# ATmega128RFA1-dev.net
KiCad netlist of a schematic drawn in EAGLE
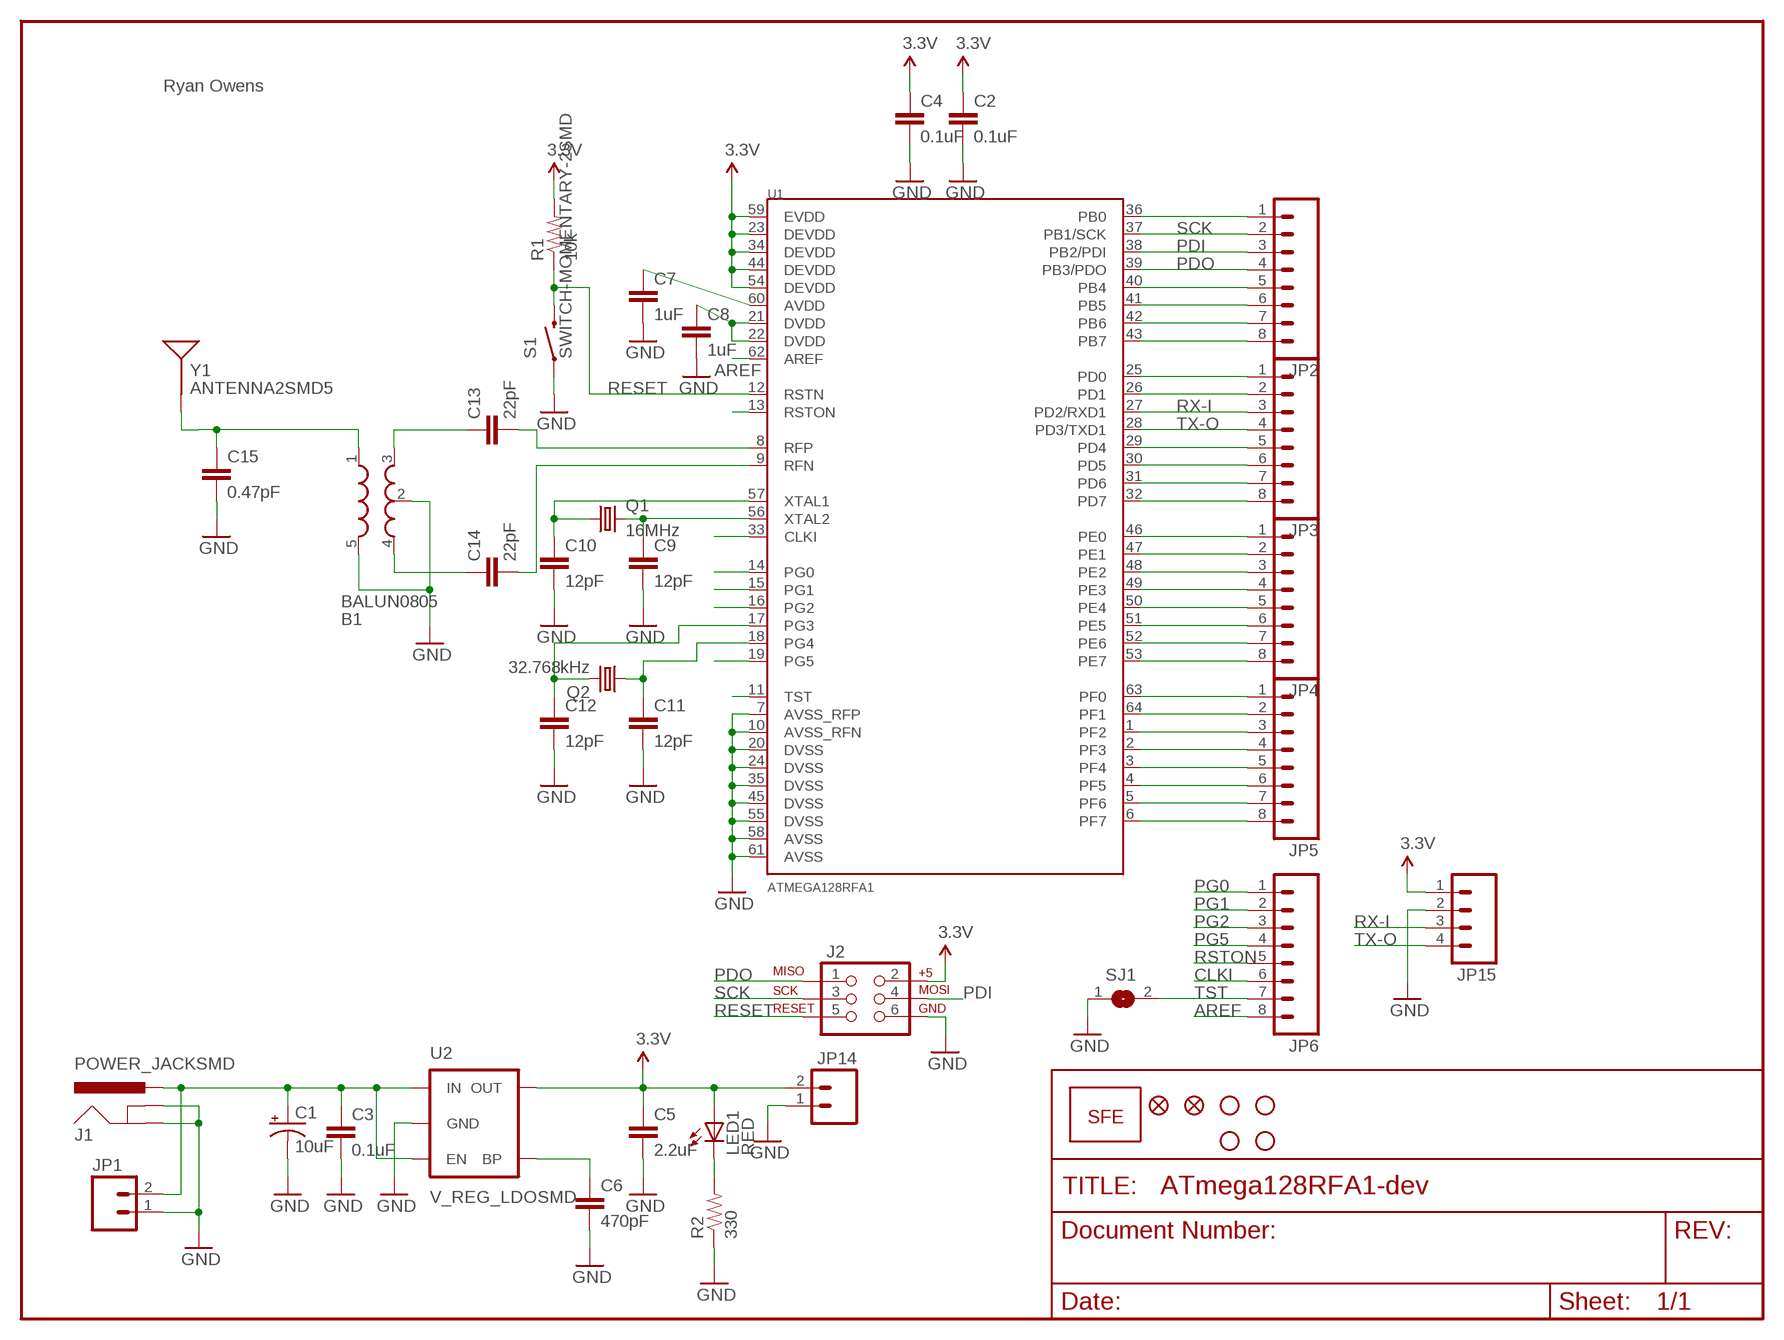
[diagram p0: schematic, sheet 1]

(export (version "E")
  (design (tool "Eeschema 10.0.6"))
  (components
    (comp (ref "B1")
      (value "BALUN0805")
      (footprint "eagle-import:BALUN")
      (libsource (lib "eagle-import") (part "BALUN0805"))
    )
    (comp (ref "C1")
      (value "10uF")
      (footprint "eagle-import:EIA3216")
      (libsource (lib "eagle-import") (part "CAP_POL1206"))
    )
    (comp (ref "C2")
      (value "0.1uF")
      (footprint "eagle-import:0603-CAP")
      (libsource (lib "eagle-import") (part "CAP0603-CAP"))
    )
    (comp (ref "C3")
      (value "0.1uF")
      (footprint "eagle-import:0603-CAP")
      (libsource (lib "eagle-import") (part "CAP0603-CAP"))
    )
    (comp (ref "C4")
      (value "0.1uF")
      (footprint "eagle-import:0603-CAP")
      (libsource (lib "eagle-import") (part "CAP0603-CAP"))
    )
    (comp (ref "C5")
      (value "2.2uF")
      (footprint "eagle-import:0603-CAP")
      (libsource (lib "eagle-import") (part "CAP0603-CAP"))
    )
    (comp (ref "C6")
      (value "470pF")
      (footprint "eagle-import:0603-CAP")
      (libsource (lib "eagle-import") (part "CAP0603-CAP"))
    )
    (comp (ref "C7")
      (value "1uF")
      (footprint "eagle-import:0805")
      (libsource (lib "eagle-import") (part "CAP0805"))
    )
    (comp (ref "C8")
      (value "1uF")
      (footprint "eagle-import:0805")
      (libsource (lib "eagle-import") (part "CAP0805"))
    )
    (comp (ref "C9")
      (value "12pF")
      (footprint "eagle-import:0603-CAP")
      (libsource (lib "eagle-import") (part "CAP0603-CAP"))
    )
    (comp (ref "C10")
      (value "12pF")
      (footprint "eagle-import:0603-CAP")
      (libsource (lib "eagle-import") (part "CAP0603-CAP"))
    )
    (comp (ref "C11")
      (value "12pF")
      (footprint "eagle-import:0603-CAP")
      (libsource (lib "eagle-import") (part "CAP0603-CAP"))
    )
    (comp (ref "C12")
      (value "12pF")
      (footprint "eagle-import:0603-CAP")
      (libsource (lib "eagle-import") (part "CAP0603-CAP"))
    )
    (comp (ref "C13")
      (value "22pF")
      (footprint "eagle-import:0603-CAP")
      (libsource (lib "eagle-import") (part "CAP0603-CAP"))
    )
    (comp (ref "C14")
      (value "22pF")
      (footprint "eagle-import:0603-CAP")
      (libsource (lib "eagle-import") (part "CAP0603-CAP"))
    )
    (comp (ref "C15")
      (value "0.47pF")
      (footprint "eagle-import:0603-CAP")
      (libsource (lib "eagle-import") (part "CAP0603-CAP"))
    )
    (comp (ref "J1")
      (value "POWER_JACKSMD")
      (footprint "eagle-import:POWER_JACK_SMD")
      (libsource (lib "eagle-import") (part "POWER_JACKSMD"))
    )
    (comp (ref "J2")
      (value "AVR_SPI_PRG_6PTH")
      (footprint "eagle-import:2X3")
      (libsource (lib "eagle-import") (part "AVR_SPI_PRG_6PTH"))
    )
    (comp (ref "JP1")
      (value "M02PTH")
      (footprint "eagle-import:1X02")
      (libsource (lib "eagle-import") (part "M02PTH"))
    )
    (comp (ref "JP2")
      (value "M08")
      (footprint "eagle-import:1X08")
      (libsource (lib "eagle-import") (part "M08"))
    )
    (comp (ref "JP3")
      (value "M08")
      (footprint "eagle-import:1X08")
      (libsource (lib "eagle-import") (part "M08"))
    )
    (comp (ref "JP4")
      (value "M08")
      (footprint "eagle-import:1X08")
      (libsource (lib "eagle-import") (part "M08"))
    )
    (comp (ref "JP5")
      (value "M08")
      (footprint "eagle-import:1X08")
      (libsource (lib "eagle-import") (part "M08"))
    )
    (comp (ref "JP6")
      (value "M08")
      (footprint "eagle-import:1X08")
      (libsource (lib "eagle-import") (part "M08"))
    )
    (comp (ref "JP7")
      (value "LOGO-SFENEW")
      (footprint "eagle-import:SFE-NEW-WEBLOGO")
      (libsource (lib "eagle-import") (part "LOGO-SFENEW"))
    )
    (comp (ref "JP8")
      (value "FIDUCIAL1X2")
      (footprint "eagle-import:FIDUCIAL-1X2")
      (libsource (lib "eagle-import") (part "FIDUCIAL1X2"))
    )
    (comp (ref "JP9")
      (value "FIDUCIAL1X2")
      (footprint "eagle-import:FIDUCIAL-1X2")
      (libsource (lib "eagle-import") (part "FIDUCIAL1X2"))
    )
    (comp (ref "JP10")
      (value "STAND-OFF")
      (footprint "eagle-import:STAND-OFF")
      (libsource (lib "eagle-import") (part "STAND-OFF"))
    )
    (comp (ref "JP11")
      (value "STAND-OFF")
      (footprint "eagle-import:STAND-OFF")
      (libsource (lib "eagle-import") (part "STAND-OFF"))
    )
    (comp (ref "JP12")
      (value "STAND-OFF")
      (footprint "eagle-import:STAND-OFF")
      (libsource (lib "eagle-import") (part "STAND-OFF"))
    )
    (comp (ref "JP13")
      (value "STAND-OFF")
      (footprint "eagle-import:STAND-OFF")
      (libsource (lib "eagle-import") (part "STAND-OFF"))
    )
    (comp (ref "JP14")
      (value "M02PTH")
      (footprint "eagle-import:1X02")
      (libsource (lib "eagle-import") (part "M02PTH"))
    )
    (comp (ref "JP15")
      (value "M04PTH")
      (footprint "eagle-import:1X04")
      (libsource (lib "eagle-import") (part "M04PTH"))
    )
    (comp (ref "LED1")
      (value "RED")
      (footprint "eagle-import:LED-0603")
      (libsource (lib "eagle-import") (part "LED0603"))
    )
    (comp (ref "Q1")
      (value "16MHz")
      (footprint "eagle-import:CRYSTAL-SMD-5X3")
      (libsource (lib "eagle-import") (part "CRYSTAL5X3"))
    )
    (comp (ref "Q2")
      (value "32.768kHz")
      (footprint "eagle-import:CRYSTAL-32KHZ-SMD")
      (libsource (lib "eagle-import") (part "CRYSTAL32-SMD"))
    )
    (comp (ref "R1")
      (value "10k")
      (footprint "eagle-import:0603-RES")
      (libsource (lib "eagle-import") (part "RESISTOR0603-RES"))
    )
    (comp (ref "R2")
      (value "330")
      (footprint "eagle-import:0603-RES")
      (libsource (lib "eagle-import") (part "RESISTOR0603-RES"))
    )
    (comp (ref "S1")
      (value "SWITCH-MOMENTARY-2SMD")
      (footprint "eagle-import:TACTILE_SWITCH_SMD")
      (libsource (lib "eagle-import") (part "SWITCH-MOMENTARY-2SMD"))
    )
    (comp (ref "SJ1") (value "SJ") (footprint "eagle-import:SJ") (libsource (lib "eagle-import") (part "SJ")))
    (comp (ref "U1")
      (value "ATMEGA128RFA1")
      (footprint "eagle-import:QFN-64")
      (libsource (lib "eagle-import") (part "ATMEGA128RFA1"))
    )
    (comp (ref "U2")
      (value "V_REG_LDOSMD")
      (footprint "eagle-import:SOT23-5")
      (libsource (lib "eagle-import") (part "V_REG_LDOSMD"))
    )
    (comp (ref "Y1")
      (value "ANTENNA2SMD5")
      (footprint "eagle-import:ANTENNA-CHIP5")
      (libsource (lib "eagle-import") (part "ANTENNA2SMD5"))
    )
  )
  (nets
    (net (code "1") (name "/AREF") (class "Default")
      (node (ref "JP6") (pin "8") (pinfunction "8_8") (pintype "passive"))
      (node (ref "U1") (pin "62") (pinfunction "AREF_62") (pintype "bidirectional"))
    )
    (net (code "2") (name "/CLKI") (class "Default")
      (node (ref "JP6") (pin "6") (pinfunction "6_6") (pintype "passive"))
      (node (ref "U1") (pin "33") (pinfunction "CLKI_33") (pintype "bidirectional"))
    )
    (net (code "3") (name "/PDI") (class "Default")
      (node (ref "J2") (pin "4") (pinfunction "4_4") (pintype "passive"))
      (node (ref "JP2") (pin "3") (pinfunction "3_3") (pintype "passive"))
      (node (ref "U1") (pin "38") (pinfunction "PB2/PDI_38") (pintype "bidirectional"))
    )
    (net (code "4") (name "/PDO") (class "Default")
      (node (ref "J2") (pin "1") (pinfunction "1_1") (pintype "passive"))
      (node (ref "JP2") (pin "4") (pinfunction "4_4") (pintype "passive"))
      (node (ref "U1") (pin "39") (pinfunction "PB3/PDO_39") (pintype "bidirectional"))
    )
    (net (code "5") (name "/PG0") (class "Default")
      (node (ref "JP6") (pin "1") (pinfunction "1_1") (pintype "passive"))
      (node (ref "U1") (pin "14") (pinfunction "PG0_14") (pintype "bidirectional"))
    )
    (net (code "6") (name "/PG1") (class "Default")
      (node (ref "JP6") (pin "2") (pinfunction "2_2") (pintype "passive"))
      (node (ref "U1") (pin "15") (pinfunction "PG1_15") (pintype "bidirectional"))
    )
    (net (code "7") (name "/PG2") (class "Default")
      (node (ref "JP6") (pin "3") (pinfunction "3_3") (pintype "passive"))
      (node (ref "U1") (pin "16") (pinfunction "PG2_16") (pintype "bidirectional"))
    )
    (net (code "8") (name "/PG5") (class "Default")
      (node (ref "JP6") (pin "4") (pinfunction "4_4") (pintype "passive"))
      (node (ref "U1") (pin "19") (pinfunction "PG5_19") (pintype "bidirectional"))
    )
    (net (code "9") (name "/RESET") (class "Default")
      (node (ref "J2") (pin "5") (pinfunction "5_5") (pintype "passive"))
      (node (ref "R1") (pin "1") (pinfunction "1_1") (pintype "passive"))
      (node (ref "S1") (pin "3") (pinfunction "2_3") (pintype "passive"))
      (node (ref "U1") (pin "12") (pinfunction "RSTN_12") (pintype "bidirectional"))
    )
    (net (code "10") (name "/RSTON") (class "Default")
      (node (ref "JP6") (pin "5") (pinfunction "5_5") (pintype "passive"))
      (node (ref "U1") (pin "13") (pinfunction "RSTON_13") (pintype "bidirectional"))
    )
    (net (code "11") (name "/RX-I") (class "Default")
      (node (ref "JP15") (pin "3") (pinfunction "3_3") (pintype "passive"))
      (node (ref "JP3") (pin "3") (pinfunction "3_3") (pintype "passive"))
      (node (ref "U1") (pin "27") (pinfunction "PD2/RXD1_27") (pintype "bidirectional"))
    )
    (net (code "12") (name "/SCK") (class "Default")
      (node (ref "J2") (pin "3") (pinfunction "3_3") (pintype "passive"))
      (node (ref "JP2") (pin "2") (pinfunction "2_2") (pintype "passive"))
      (node (ref "U1") (pin "37") (pinfunction "PB1/SCK_37") (pintype "bidirectional"))
    )
    (net (code "13") (name "/TST") (class "Default")
      (node (ref "JP6") (pin "7") (pinfunction "7_7") (pintype "passive"))
      (node (ref "SJ1") (pin "2") (pinfunction "2_2") (pintype "passive"))
      (node (ref "U1") (pin "11") (pinfunction "TST_11") (pintype "bidirectional"))
    )
    (net (code "14") (name "/TX-O") (class "Default")
      (node (ref "JP15") (pin "4") (pinfunction "4_4") (pintype "passive"))
      (node (ref "JP3") (pin "4") (pinfunction "4_4") (pintype "passive"))
      (node (ref "U1") (pin "28") (pinfunction "PD3/TXD1_28") (pintype "bidirectional"))
    )
    (net (code "15") (name "3.3V") (class "Default")
      (node (ref "C2") (pin "1") (pinfunction "1_1") (pintype "passive"))
      (node (ref "C4") (pin "1") (pinfunction "1_1") (pintype "passive"))
      (node (ref "C5") (pin "1") (pinfunction "1_1") (pintype "passive"))
      (node (ref "J2") (pin "2") (pinfunction "2_2") (pintype "passive"))
      (node (ref "JP14") (pin "2") (pinfunction "2_2") (pintype "passive"))
      (node (ref "JP15") (pin "1") (pinfunction "1_1") (pintype "passive"))
      (node (ref "LED1") (pin "A") (pinfunction "A_A") (pintype "passive"))
      (node (ref "R1") (pin "2") (pinfunction "2_2") (pintype "passive"))
      (node (ref "U1") (pin "23") (pinfunction "DEVDD_23") (pintype "bidirectional"))
      (node (ref "U1") (pin "34") (pinfunction "DEVDD_34") (pintype "bidirectional"))
      (node (ref "U1") (pin "44") (pinfunction "DEVDD_44") (pintype "bidirectional"))
      (node (ref "U1") (pin "54") (pinfunction "DEVDD_54") (pintype "bidirectional"))
      (node (ref "U1") (pin "59") (pinfunction "EVDD_59") (pintype "bidirectional"))
      (node (ref "U2") (pin "5") (pinfunction "OUT_5") (pintype "passive"))
    )
    (net (code "16") (name "GND") (class "Default")
      (node (ref "B1") (pin "2") (pinfunction "GND_2") (pintype "bidirectional"))
      (node (ref "B1") (pin "5") (pinfunction "GND_5") (pintype "bidirectional"))
      (node (ref "C1") (pin "C") (pinfunction "-_C") (pintype "passive"))
      (node (ref "C10") (pin "2") (pinfunction "2_2") (pintype "passive"))
      (node (ref "C11") (pin "2") (pinfunction "2_2") (pintype "passive"))
      (node (ref "C12") (pin "2") (pinfunction "2_2") (pintype "passive"))
      (node (ref "C15") (pin "2") (pinfunction "2_2") (pintype "passive"))
      (node (ref "C2") (pin "2") (pinfunction "2_2") (pintype "passive"))
      (node (ref "C3") (pin "2") (pinfunction "2_2") (pintype "passive"))
      (node (ref "C4") (pin "2") (pinfunction "2_2") (pintype "passive"))
      (node (ref "C5") (pin "2") (pinfunction "2_2") (pintype "passive"))
      (node (ref "C6") (pin "2") (pinfunction "2_2") (pintype "passive"))
      (node (ref "C7") (pin "2") (pinfunction "2_2") (pintype "passive"))
      (node (ref "C8") (pin "2") (pinfunction "2_2") (pintype "passive"))
      (node (ref "C9") (pin "2") (pinfunction "2_2") (pintype "passive"))
      (node (ref "J1") (pin "GND") (pinfunction "GNDBREAK_GND") (pintype "bidirectional"))
      (node (ref "J1") (pin "P$4") (pinfunction "GND_P$4") (pintype "bidirectional"))
      (node (ref "J2") (pin "6") (pinfunction "6_6") (pintype "passive"))
      (node (ref "JP1") (pin "1") (pinfunction "1_1") (pintype "passive"))
      (node (ref "JP14") (pin "1") (pinfunction "1_1") (pintype "passive"))
      (node (ref "JP15") (pin "2") (pinfunction "2_2") (pintype "passive"))
      (node (ref "R2") (pin "1") (pinfunction "1_1") (pintype "passive"))
      (node (ref "S1") (pin "1") (pinfunction "1_1") (pintype "passive"))
      (node (ref "SJ1") (pin "1") (pinfunction "1_1") (pintype "passive"))
      (node (ref "U1") (pin "10") (pinfunction "AVSS_RFN_10") (pintype "bidirectional"))
      (node (ref "U1") (pin "20") (pinfunction "DVSS_20") (pintype "bidirectional"))
      (node (ref "U1") (pin "24") (pinfunction "DVSS_24") (pintype "bidirectional"))
      (node (ref "U1") (pin "35") (pinfunction "DVSS_35") (pintype "bidirectional"))
      (node (ref "U1") (pin "45") (pinfunction "DVSS_45") (pintype "bidirectional"))
      (node (ref "U1") (pin "55") (pinfunction "DVSS_55") (pintype "bidirectional"))
      (node (ref "U1") (pin "58") (pinfunction "AVSS_58") (pintype "bidirectional"))
      (node (ref "U1") (pin "61") (pinfunction "AVSS_61") (pintype "bidirectional"))
      (node (ref "U1") (pin "7") (pinfunction "AVSS_RFP_7") (pintype "bidirectional"))
      (node (ref "U2") (pin "2") (pinfunction "GND_2") (pintype "input"))
    )
    (net (code "17") (name "Net-(B1-IN)") (class "Default")
      (node (ref "B1") (pin "1") (pinfunction "IN_1") (pintype "bidirectional"))
      (node (ref "C15") (pin "1") (pinfunction "1_1") (pintype "passive"))
      (node (ref "Y1") (pin "FEED") (pinfunction "SIGNAL_FEED") (pintype "bidirectional"))
    )
    (net (code "18") (name "Net-(B1-OUT1)") (class "Default")
      (node (ref "B1") (pin "3") (pinfunction "OUT1_3") (pintype "bidirectional"))
      (node (ref "C13") (pin "1") (pinfunction "1_1") (pintype "passive"))
    )
    (net (code "19") (name "Net-(B1-OUT2)") (class "Default")
      (node (ref "B1") (pin "4") (pinfunction "OUT2_4") (pintype "bidirectional"))
      (node (ref "C14") (pin "1") (pinfunction "1_1") (pintype "passive"))
    )
    (net (code "20") (name "Net-(C1-+)") (class "Default")
      (node (ref "C1") (pin "A") (pinfunction "+_A") (pintype "passive"))
      (node (ref "C3") (pin "1") (pinfunction "1_1") (pintype "passive"))
      (node (ref "J1") (pin "VIN0") (pinfunction "PWR_VIN0") (pintype "bidirectional"))
      (node (ref "JP1") (pin "2") (pinfunction "2_2") (pintype "passive"))
      (node (ref "U2") (pin "1") (pinfunction "IN_1") (pintype "input"))
      (node (ref "U2") (pin "3") (pinfunction "EN_3") (pintype "input"))
    )
    (net (code "21") (name "Net-(C8-Pad1)") (class "Default")
      (node (ref "C8") (pin "1") (pinfunction "1_1") (pintype "passive"))
      (node (ref "U1") (pin "21") (pinfunction "DVDD_21") (pintype "bidirectional"))
      (node (ref "U1") (pin "22") (pinfunction "DVDD_22") (pintype "bidirectional"))
    )
    (net (code "22") (name "Net-(LED1-PadC)") (class "Default")
      (node (ref "LED1") (pin "C") (pinfunction "C_C") (pintype "passive"))
      (node (ref "R2") (pin "2") (pinfunction "2_2") (pintype "passive"))
    )
    (net (code "23") (name "Net-(Q1-2)") (class "Default")
      (node (ref "C9") (pin "1") (pinfunction "1_1") (pintype "passive"))
      (node (ref "Q1") (pin "3") (pinfunction "2_3") (pintype "passive"))
      (node (ref "U1") (pin "56") (pinfunction "XTAL2_56") (pintype "bidirectional"))
    )
    (net (code "24") (name "Net-(Q2-1)") (class "Default")
      (node (ref "C11") (pin "1") (pinfunction "1_1") (pintype "passive"))
      (node (ref "Q2") (pin "X1") (pinfunction "1_X1") (pintype "passive"))
      (node (ref "U1") (pin "18") (pinfunction "PG4_18") (pintype "bidirectional"))
    )
    (net (code "25") (name "Net-(Q2-2)") (class "Default")
      (node (ref "C12") (pin "1") (pinfunction "1_1") (pintype "passive"))
      (node (ref "Q2") (pin "X2") (pinfunction "2_X2") (pintype "passive"))
      (node (ref "U1") (pin "17") (pinfunction "PG3_17") (pintype "bidirectional"))
    )
    (net (code "26") (name "Net-(U1-AVDD)") (class "Default")
      (node (ref "C7") (pin "1") (pinfunction "1_1") (pintype "passive"))
      (node (ref "U1") (pin "60") (pinfunction "AVDD_60") (pintype "bidirectional"))
    )
    (net (code "27") (name "Net-(U1-PB0)") (class "Default")
      (node (ref "JP2") (pin "1") (pinfunction "1_1") (pintype "passive"))
      (node (ref "U1") (pin "36") (pinfunction "PB0_36") (pintype "bidirectional"))
    )
    (net (code "28") (name "Net-(U1-PB4)") (class "Default")
      (node (ref "JP2") (pin "5") (pinfunction "5_5") (pintype "passive"))
      (node (ref "U1") (pin "40") (pinfunction "PB4_40") (pintype "bidirectional"))
    )
    (net (code "29") (name "Net-(U1-PB5)") (class "Default")
      (node (ref "JP2") (pin "6") (pinfunction "6_6") (pintype "passive"))
      (node (ref "U1") (pin "41") (pinfunction "PB5_41") (pintype "bidirectional"))
    )
    (net (code "30") (name "Net-(U1-PB6)") (class "Default")
      (node (ref "JP2") (pin "7") (pinfunction "7_7") (pintype "passive"))
      (node (ref "U1") (pin "42") (pinfunction "PB6_42") (pintype "bidirectional"))
    )
    (net (code "31") (name "Net-(U1-PB7)") (class "Default")
      (node (ref "JP2") (pin "8") (pinfunction "8_8") (pintype "passive"))
      (node (ref "U1") (pin "43") (pinfunction "PB7_43") (pintype "bidirectional"))
    )
    (net (code "32") (name "Net-(U1-PD0)") (class "Default")
      (node (ref "JP3") (pin "1") (pinfunction "1_1") (pintype "passive"))
      (node (ref "U1") (pin "25") (pinfunction "PD0_25") (pintype "bidirectional"))
    )
    (net (code "33") (name "Net-(U1-PD1)") (class "Default")
      (node (ref "JP3") (pin "2") (pinfunction "2_2") (pintype "passive"))
      (node (ref "U1") (pin "26") (pinfunction "PD1_26") (pintype "bidirectional"))
    )
    (net (code "34") (name "Net-(U1-PD4)") (class "Default")
      (node (ref "JP3") (pin "5") (pinfunction "5_5") (pintype "passive"))
      (node (ref "U1") (pin "29") (pinfunction "PD4_29") (pintype "bidirectional"))
    )
    (net (code "35") (name "Net-(U1-PD5)") (class "Default")
      (node (ref "JP3") (pin "6") (pinfunction "6_6") (pintype "passive"))
      (node (ref "U1") (pin "30") (pinfunction "PD5_30") (pintype "bidirectional"))
    )
    (net (code "36") (name "Net-(U1-PD6)") (class "Default")
      (node (ref "JP3") (pin "7") (pinfunction "7_7") (pintype "passive"))
      (node (ref "U1") (pin "31") (pinfunction "PD6_31") (pintype "bidirectional"))
    )
    (net (code "37") (name "Net-(U1-PD7)") (class "Default")
      (node (ref "JP3") (pin "8") (pinfunction "8_8") (pintype "passive"))
      (node (ref "U1") (pin "32") (pinfunction "PD7_32") (pintype "bidirectional"))
    )
    (net (code "38") (name "Net-(U1-PE0)") (class "Default")
      (node (ref "JP4") (pin "1") (pinfunction "1_1") (pintype "passive"))
      (node (ref "U1") (pin "46") (pinfunction "PE0_46") (pintype "bidirectional"))
    )
    (net (code "39") (name "Net-(U1-PE1)") (class "Default")
      (node (ref "JP4") (pin "2") (pinfunction "2_2") (pintype "passive"))
      (node (ref "U1") (pin "47") (pinfunction "PE1_47") (pintype "bidirectional"))
    )
    (net (code "40") (name "Net-(U1-PE2)") (class "Default")
      (node (ref "JP4") (pin "3") (pinfunction "3_3") (pintype "passive"))
      (node (ref "U1") (pin "48") (pinfunction "PE2_48") (pintype "bidirectional"))
    )
    (net (code "41") (name "Net-(U1-PE3)") (class "Default")
      (node (ref "JP4") (pin "4") (pinfunction "4_4") (pintype "passive"))
      (node (ref "U1") (pin "49") (pinfunction "PE3_49") (pintype "bidirectional"))
    )
    (net (code "42") (name "Net-(U1-PE4)") (class "Default")
      (node (ref "JP4") (pin "5") (pinfunction "5_5") (pintype "passive"))
      (node (ref "U1") (pin "50") (pinfunction "PE4_50") (pintype "bidirectional"))
    )
    (net (code "43") (name "Net-(U1-PE5)") (class "Default")
      (node (ref "JP4") (pin "6") (pinfunction "6_6") (pintype "passive"))
      (node (ref "U1") (pin "51") (pinfunction "PE5_51") (pintype "bidirectional"))
    )
    (net (code "44") (name "Net-(U1-PE6)") (class "Default")
      (node (ref "JP4") (pin "7") (pinfunction "7_7") (pintype "passive"))
      (node (ref "U1") (pin "52") (pinfunction "PE6_52") (pintype "bidirectional"))
    )
    (net (code "45") (name "Net-(U1-PE7)") (class "Default")
      (node (ref "JP4") (pin "8") (pinfunction "8_8") (pintype "passive"))
      (node (ref "U1") (pin "53") (pinfunction "PE7_53") (pintype "bidirectional"))
    )
    (net (code "46") (name "Net-(U1-PF0)") (class "Default")
      (node (ref "JP5") (pin "1") (pinfunction "1_1") (pintype "passive"))
      (node (ref "U1") (pin "63") (pinfunction "PF0_63") (pintype "bidirectional"))
    )
    (net (code "47") (name "Net-(U1-PF1)") (class "Default")
      (node (ref "JP5") (pin "2") (pinfunction "2_2") (pintype "passive"))
      (node (ref "U1") (pin "64") (pinfunction "PF1_64") (pintype "bidirectional"))
    )
    (net (code "48") (name "Net-(U1-PF2)") (class "Default")
      (node (ref "JP5") (pin "3") (pinfunction "3_3") (pintype "passive"))
      (node (ref "U1") (pin "1") (pinfunction "PF2_1") (pintype "bidirectional"))
    )
    (net (code "49") (name "Net-(U1-PF3)") (class "Default")
      (node (ref "JP5") (pin "4") (pinfunction "4_4") (pintype "passive"))
      (node (ref "U1") (pin "2") (pinfunction "PF3_2") (pintype "bidirectional"))
    )
    (net (code "50") (name "Net-(U1-PF4)") (class "Default")
      (node (ref "JP5") (pin "5") (pinfunction "5_5") (pintype "passive"))
      (node (ref "U1") (pin "3") (pinfunction "PF4_3") (pintype "bidirectional"))
    )
    (net (code "51") (name "Net-(U1-PF5)") (class "Default")
      (node (ref "JP5") (pin "6") (pinfunction "6_6") (pintype "passive"))
      (node (ref "U1") (pin "4") (pinfunction "PF5_4") (pintype "bidirectional"))
    )
    (net (code "52") (name "Net-(U1-PF6)") (class "Default")
      (node (ref "JP5") (pin "7") (pinfunction "7_7") (pintype "passive"))
      (node (ref "U1") (pin "5") (pinfunction "PF6_5") (pintype "bidirectional"))
    )
    (net (code "53") (name "Net-(U1-PF7)") (class "Default")
      (node (ref "JP5") (pin "8") (pinfunction "8_8") (pintype "passive"))
      (node (ref "U1") (pin "6") (pinfunction "PF7_6") (pintype "bidirectional"))
    )
    (net (code "54") (name "Net-(U1-RFN)") (class "Default")
      (node (ref "C14") (pin "2") (pinfunction "2_2") (pintype "passive"))
      (node (ref "U1") (pin "9") (pinfunction "RFN_9") (pintype "bidirectional"))
    )
    (net (code "55") (name "Net-(U1-RFP)") (class "Default")
      (node (ref "C13") (pin "2") (pinfunction "2_2") (pintype "passive"))
      (node (ref "U1") (pin "8") (pinfunction "RFP_8") (pintype "bidirectional"))
    )
    (net (code "56") (name "Net-(U1-XTAL1)") (class "Default")
      (node (ref "C10") (pin "1") (pinfunction "1_1") (pintype "passive"))
      (node (ref "Q1") (pin "1") (pinfunction "1_1") (pintype "passive"))
      (node (ref "U1") (pin "57") (pinfunction "XTAL1_57") (pintype "bidirectional"))
    )
    (net (code "57") (name "Net-(U2-BP)") (class "Default")
      (node (ref "C6") (pin "1") (pinfunction "1_1") (pintype "passive"))
      (node (ref "U2") (pin "4") (pinfunction "BP_4") (pintype "input"))
    )
  )
)
